# Bank1_DDR.net
KiCad netlist of a schematic drawn in Altium Designer
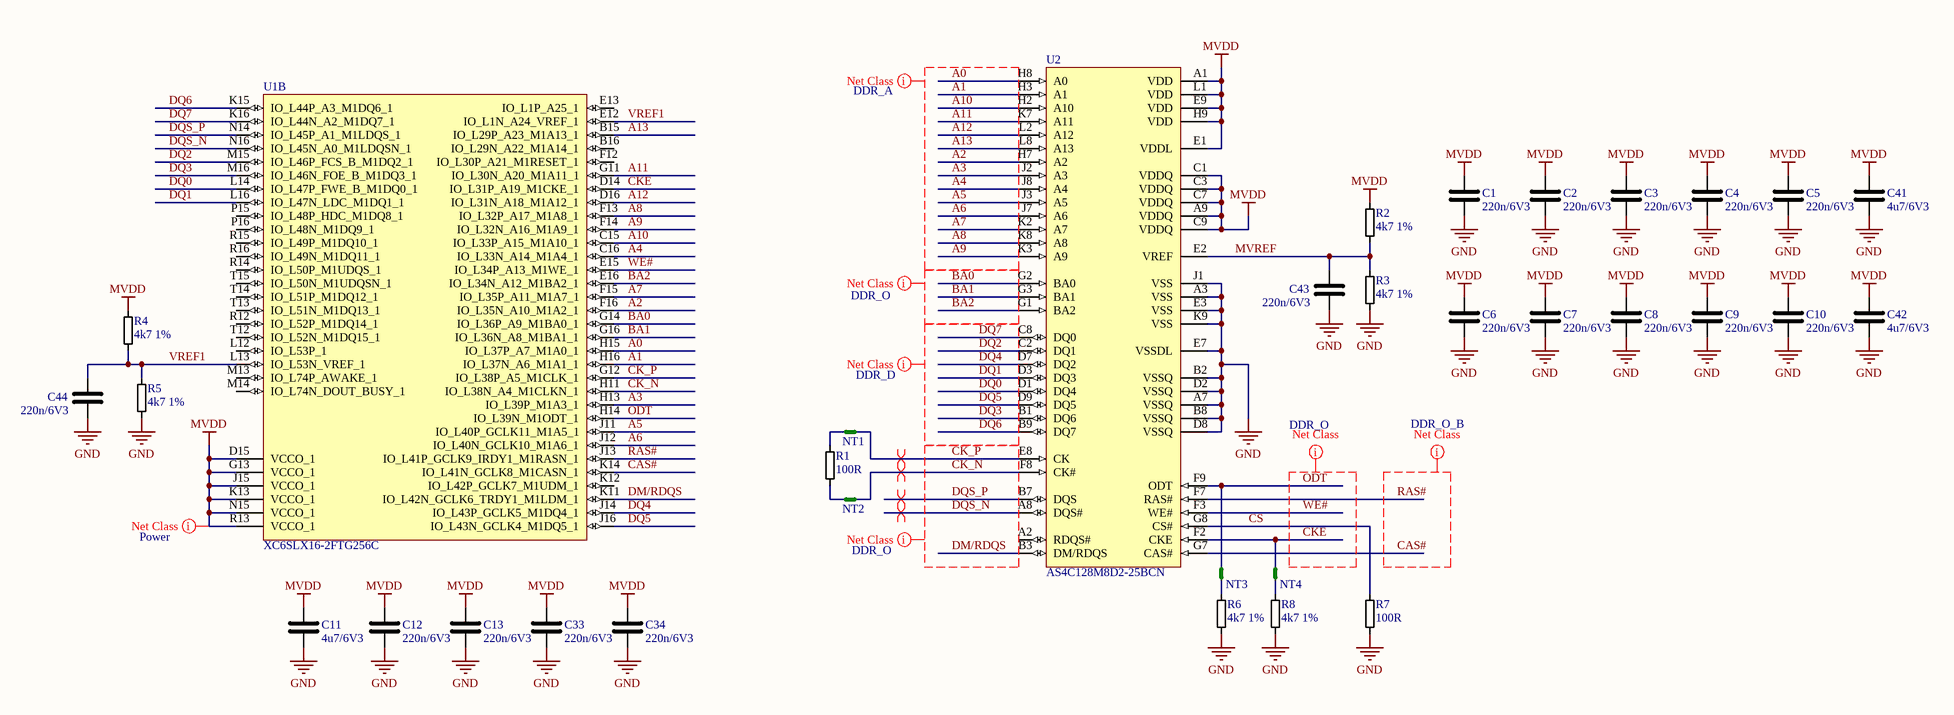
[diagram p0: Bank1_DDR.SchDoc]

(export (version "E")
  (design (tool "Eeschema 10.0.6"))
  (components
    (comp (ref "C1") (value "220n/6V3") (footprint "C0402_N") (libsource (lib "niceCircuits") (part "C")))
    (comp (ref "C2") (value "220n/6V3") (footprint "C0402_N") (libsource (lib "niceCircuits") (part "C")))
    (comp (ref "C3") (value "220n/6V3") (footprint "C0402_N") (libsource (lib "niceCircuits") (part "C")))
    (comp (ref "C4") (value "220n/6V3") (footprint "C0402_N") (libsource (lib "niceCircuits") (part "C")))
    (comp (ref "C5") (value "220n/6V3") (footprint "C0402_N") (libsource (lib "niceCircuits") (part "C")))
    (comp (ref "C6") (value "220n/6V3") (footprint "C0402_N") (libsource (lib "niceCircuits") (part "C")))
    (comp (ref "C7") (value "220n/6V3") (footprint "C0402_N") (libsource (lib "niceCircuits") (part "C")))
    (comp (ref "C8") (value "220n/6V3") (footprint "C0402_N") (libsource (lib "niceCircuits") (part "C")))
    (comp (ref "C9") (value "220n/6V3") (footprint "C0402_N") (libsource (lib "niceCircuits") (part "C")))
    (comp (ref "C10") (value "220n/6V3") (footprint "C0402_N") (libsource (lib "niceCircuits") (part "C")))
    (comp (ref "C11") (value "4u7/6V3") (footprint "C0805_N") (libsource (lib "niceCircuits") (part "C")))
    (comp (ref "C12") (value "220n/6V3") (footprint "C0402_N") (libsource (lib "niceCircuits") (part "C")))
    (comp (ref "C13") (value "220n/6V3") (footprint "C0402_N") (libsource (lib "niceCircuits") (part "C")))
    (comp (ref "C33") (value "220n/6V3") (footprint "C0402_N") (libsource (lib "niceCircuits") (part "C")))
    (comp (ref "C34") (value "220n/6V3") (footprint "C0402_N") (libsource (lib "niceCircuits") (part "C")))
    (comp (ref "C41") (value "4u7/6V3") (footprint "C0805_N") (libsource (lib "niceCircuits") (part "C")))
    (comp (ref "C42") (value "4u7/6V3") (footprint "C0805_N") (libsource (lib "niceCircuits") (part "C")))
    (comp (ref "C43") (value "220n/6V3") (footprint "C0402_N") (libsource (lib "niceCircuits") (part "C")))
    (comp (ref "C44") (value "220n/6V3") (footprint "C0402_N") (libsource (lib "niceCircuits") (part "C")))
    (comp (ref "NT1")
      (value "NET TIE")
      (footprint "NET_TIE_5MIL_2")
      (libsource (lib "niceCircuits") (part "NET TIE"))
    )
    (comp (ref "NT2")
      (value "NET TIE")
      (footprint "NET_TIE_5MIL_2")
      (libsource (lib "niceCircuits") (part "NET TIE"))
    )
    (comp (ref "NT3")
      (value "NET TIE")
      (footprint "NET_TIE_5MIL_2")
      (libsource (lib "niceCircuits") (part "NET TIE"))
    )
    (comp (ref "NT4")
      (value "NET TIE")
      (footprint "NET_TIE_5MIL_2")
      (libsource (lib "niceCircuits") (part "NET TIE"))
    )
    (comp (ref "R1") (value "100R") (footprint "R0402_N") (libsource (lib "niceCircuits") (part "R")))
    (comp (ref "R2") (value "4k7 1%") (footprint "R0402_N") (libsource (lib "niceCircuits") (part "R")))
    (comp (ref "R3") (value "4k7 1%") (footprint "R0402_N") (libsource (lib "niceCircuits") (part "R")))
    (comp (ref "R4") (value "4k7 1%") (footprint "R0402_N") (libsource (lib "niceCircuits") (part "R")))
    (comp (ref "R5") (value "4k7 1%") (footprint "R0402_N") (libsource (lib "niceCircuits") (part "R")))
    (comp (ref "R6") (value "4k7 1%") (footprint "R0402_N") (libsource (lib "niceCircuits") (part "R")))
    (comp (ref "R7") (value "100R") (footprint "R0402_N") (libsource (lib "niceCircuits") (part "R")))
    (comp (ref "R8") (value "4k7 1%") (footprint "R0402_N") (libsource (lib "niceCircuits") (part "R")))
    (comp (ref "U1")
      (value "XC6SLX16-2FTG256C")
      (footprint "Xilinx_FT256_L")
      (libsource (lib "niceCircuits") (part "XC6SLX16-2FTG256C"))
    )
    (comp (ref "U2")
      (value "AS4C128M8D2-25BCN")
      (footprint "Alliance_FBGA60")
      (libsource (lib "niceCircuits") (part "AS4C128M8D2-25BCN"))
    )
  )
  (nets
    (net (code "1") (name "/A0") (class "Default")
      (node (ref "U1") (pin "H15") (pinfunction "IO_L37P_A7_M1A0_1_H15") (pintype "bidirectional"))
      (node (ref "U2") (pin "H8") (pinfunction "A0_H8") (pintype "input"))
    )
    (net (code "2") (name "/A1") (class "Default")
      (node (ref "U1") (pin "H16") (pinfunction "IO_L37N_A6_M1A1_1_H16") (pintype "bidirectional"))
      (node (ref "U2") (pin "H3") (pinfunction "A1_H3") (pintype "input"))
    )
    (net (code "3") (name "/A2") (class "Default")
      (node (ref "U1") (pin "F16") (pinfunction "IO_L35N_A10_M1A2_1_F16") (pintype "bidirectional"))
      (node (ref "U2") (pin "H7") (pinfunction "A2_H7") (pintype "input"))
    )
    (net (code "4") (name "/A3") (class "Default")
      (node (ref "U1") (pin "H13") (pinfunction "IO_L39P_M1A3_1_H13") (pintype "bidirectional"))
      (node (ref "U2") (pin "J2") (pinfunction "A3_J2") (pintype "input"))
    )
    (net (code "5") (name "/A4") (class "Default")
      (node (ref "U1") (pin "C16") (pinfunction "IO_L33N_A14_M1A4_1_C16") (pintype "bidirectional"))
      (node (ref "U2") (pin "J8") (pinfunction "A4_J8") (pintype "input"))
    )
    (net (code "6") (name "/A5") (class "Default")
      (node (ref "U1") (pin "J11") (pinfunction "IO_L40P_GCLK11_M1A5_1_J11") (pintype "bidirectional"))
      (node (ref "U2") (pin "J3") (pinfunction "A5_J3") (pintype "input"))
    )
    (net (code "7") (name "/A6") (class "Default")
      (node (ref "U1") (pin "J12") (pinfunction "IO_L40N_GCLK10_M1A6_1_J12") (pintype "bidirectional"))
      (node (ref "U2") (pin "J7") (pinfunction "A6_J7") (pintype "input"))
    )
    (net (code "8") (name "/A7") (class "Default")
      (node (ref "U1") (pin "F15") (pinfunction "IO_L35P_A11_M1A7_1_F15") (pintype "bidirectional"))
      (node (ref "U2") (pin "K2") (pinfunction "A7_K2") (pintype "input"))
    )
    (net (code "9") (name "/A8") (class "Default")
      (node (ref "U1") (pin "F13") (pinfunction "IO_L32P_A17_M1A8_1_F13") (pintype "bidirectional"))
      (node (ref "U2") (pin "K8") (pinfunction "A8_K8") (pintype "input"))
    )
    (net (code "10") (name "/A9") (class "Default")
      (node (ref "U1") (pin "F14") (pinfunction "IO_L32N_A16_M1A9_1_F14") (pintype "bidirectional"))
      (node (ref "U2") (pin "K3") (pinfunction "A9_K3") (pintype "input"))
    )
    (net (code "11") (name "/A10") (class "Default")
      (node (ref "U1") (pin "C15") (pinfunction "IO_L33P_A15_M1A10_1_C15") (pintype "bidirectional"))
      (node (ref "U2") (pin "H2") (pinfunction "A10_H2") (pintype "input"))
    )
    (net (code "12") (name "/A11") (class "Default")
      (node (ref "U1") (pin "G11") (pinfunction "IO_L30N_A20_M1A11_1_G11") (pintype "bidirectional"))
      (node (ref "U2") (pin "K7") (pinfunction "A11_K7") (pintype "input"))
    )
    (net (code "13") (name "/A12") (class "Default")
      (node (ref "U1") (pin "D16") (pinfunction "IO_L31N_A18_M1A12_1_D16") (pintype "bidirectional"))
      (node (ref "U2") (pin "L2") (pinfunction "A12_L2") (pintype "input"))
    )
    (net (code "14") (name "/A13") (class "Default")
      (node (ref "U1") (pin "B15") (pinfunction "IO_L29P_A23_M1A13_1_B15") (pintype "bidirectional"))
      (node (ref "U2") (pin "L8") (pinfunction "A13_L8") (pintype "input"))
    )
    (net (code "15") (name "/BA0") (class "Default")
      (node (ref "U1") (pin "G14") (pinfunction "IO_L36P_A9_M1BA0_1_G14") (pintype "bidirectional"))
      (node (ref "U2") (pin "G2") (pinfunction "BA0_G2") (pintype "input"))
    )
    (net (code "16") (name "/BA1") (class "Default")
      (node (ref "U1") (pin "G16") (pinfunction "IO_L36N_A8_M1BA1_1_G16") (pintype "bidirectional"))
      (node (ref "U2") (pin "G3") (pinfunction "BA1_G3") (pintype "input"))
    )
    (net (code "17") (name "/BA2") (class "Default")
      (node (ref "U1") (pin "E16") (pinfunction "IO_L34N_A12_M1BA2_1_E16") (pintype "bidirectional"))
      (node (ref "U2") (pin "G1") (pinfunction "BA2_G1") (pintype "input"))
    )
    (net (code "18") (name "/CAS#") (class "Default")
      (node (ref "U1") (pin "K14") (pinfunction "IO_L41N_GCLK8_M1CASN_1_K14") (pintype "bidirectional"))
      (node (ref "U2") (pin "G7") (pinfunction "CAS#_G7") (pintype "input"))
    )
    (net (code "19") (name "/CKE") (class "Default")
      (node (ref "NT4") (pin "2") (pinfunction "2_2") (pintype "passive"))
      (node (ref "U1") (pin "D14") (pinfunction "IO_L31P_A19_M1CKE_1_D14") (pintype "bidirectional"))
      (node (ref "U2") (pin "F2") (pinfunction "CKE_F2") (pintype "input"))
    )
    (net (code "20") (name "/CK_N") (class "Default")
      (node (ref "NT2") (pin "2") (pinfunction "2_2") (pintype "passive"))
      (node (ref "U1") (pin "H11") (pinfunction "IO_L38N_A4_M1CLKN_1_H11") (pintype "bidirectional"))
      (node (ref "U2") (pin "F8") (pinfunction "CK#_F8") (pintype "input"))
    )
    (net (code "21") (name "/CK_P") (class "Default")
      (node (ref "NT1") (pin "2") (pinfunction "2_2") (pintype "passive"))
      (node (ref "U1") (pin "G12") (pinfunction "IO_L38P_A5_M1CLK_1_G12") (pintype "bidirectional"))
      (node (ref "U2") (pin "E8") (pinfunction "CK_E8") (pintype "input"))
    )
    (net (code "22") (name "/CS") (class "Default")
      (node (ref "R7") (pin "1") (pinfunction "1_1") (pintype "passive"))
      (node (ref "U2") (pin "G8") (pinfunction "CS#_G8") (pintype "input"))
    )
    (net (code "23") (name "/DM{slash}RDQS") (class "Default")
      (node (ref "U1") (pin "K11") (pinfunction "IO_L42N_GCLK6_TRDY1_M1LDM_1_K11") (pintype "bidirectional"))
      (node (ref "U2") (pin "B3") (pinfunction "DM/RDQS_B3") (pintype "bidirectional"))
    )
    (net (code "24") (name "/DQ0") (class "Default")
      (node (ref "U1") (pin "L14") (pinfunction "IO_L47P_FWE_B_M1DQ0_1_L14") (pintype "bidirectional"))
      (node (ref "U2") (pin "D1") (pinfunction "DQ4_D1") (pintype "bidirectional"))
    )
    (net (code "25") (name "/DQ1") (class "Default")
      (node (ref "U1") (pin "L16") (pinfunction "IO_L47N_LDC_M1DQ1_1_L16") (pintype "bidirectional"))
      (node (ref "U2") (pin "D3") (pinfunction "DQ3_D3") (pintype "bidirectional"))
    )
    (net (code "26") (name "/DQ2") (class "Default")
      (node (ref "U1") (pin "M15") (pinfunction "IO_L46P_FCS_B_M1DQ2_1_M15") (pintype "bidirectional"))
      (node (ref "U2") (pin "C2") (pinfunction "DQ1_C2") (pintype "bidirectional"))
    )
    (net (code "27") (name "/DQ3") (class "Default")
      (node (ref "U1") (pin "M16") (pinfunction "IO_L46N_FOE_B_M1DQ3_1_M16") (pintype "bidirectional"))
      (node (ref "U2") (pin "B1") (pinfunction "DQ6_B1") (pintype "bidirectional"))
    )
    (net (code "28") (name "/DQ4") (class "Default")
      (node (ref "U1") (pin "J14") (pinfunction "IO_L43P_GCLK5_M1DQ4_1_J14") (pintype "bidirectional"))
      (node (ref "U2") (pin "D7") (pinfunction "DQ2_D7") (pintype "bidirectional"))
    )
    (net (code "29") (name "/DQ5") (class "Default")
      (node (ref "U1") (pin "J16") (pinfunction "IO_L43N_GCLK4_M1DQ5_1_J16") (pintype "bidirectional"))
      (node (ref "U2") (pin "D9") (pinfunction "DQ5_D9") (pintype "bidirectional"))
    )
    (net (code "30") (name "/DQ6") (class "Default")
      (node (ref "U1") (pin "K15") (pinfunction "IO_L44P_A3_M1DQ6_1_K15") (pintype "bidirectional"))
      (node (ref "U2") (pin "B9") (pinfunction "DQ7_B9") (pintype "bidirectional"))
    )
    (net (code "31") (name "/DQ7") (class "Default")
      (node (ref "U1") (pin "K16") (pinfunction "IO_L44N_A2_M1DQ7_1_K16") (pintype "bidirectional"))
      (node (ref "U2") (pin "C8") (pinfunction "DQ0_C8") (pintype "bidirectional"))
    )
    (net (code "32") (name "/DQS_N") (class "Default")
      (node (ref "U1") (pin "N16") (pinfunction "IO_L45N_A0_M1LDQSN_1_N16") (pintype "bidirectional"))
      (node (ref "U2") (pin "A8") (pinfunction "DQS#_A8") (pintype "bidirectional"))
    )
    (net (code "33") (name "/DQS_P") (class "Default")
      (node (ref "U1") (pin "N14") (pinfunction "IO_L45P_A1_M1LDQS_1_N14") (pintype "bidirectional"))
      (node (ref "U2") (pin "B7") (pinfunction "DQS_B7") (pintype "bidirectional"))
    )
    (net (code "34") (name "/MVREF") (class "Default")
      (node (ref "C43") (pin "2") (pinfunction "2_2") (pintype "passive"))
      (node (ref "R2") (pin "2") (pinfunction "2_2") (pintype "passive"))
      (node (ref "R3") (pin "1") (pinfunction "1_1") (pintype "passive"))
      (node (ref "U2") (pin "E2") (pinfunction "VREF_E2") (pintype "power_in"))
    )
    (net (code "35") (name "/ODT") (class "Default")
      (node (ref "NT3") (pin "2") (pinfunction "2_2") (pintype "passive"))
      (node (ref "U1") (pin "H14") (pinfunction "IO_L39N_M1ODT_1_H14") (pintype "bidirectional"))
      (node (ref "U2") (pin "F9") (pinfunction "ODT_F9") (pintype "input"))
    )
    (net (code "36") (name "/RAS#") (class "Default")
      (node (ref "U1") (pin "J13") (pinfunction "IO_L41P_GCLK9_IRDY1_M1RASN_1_J13") (pintype "bidirectional"))
      (node (ref "U2") (pin "F7") (pinfunction "RAS#_F7") (pintype "input"))
    )
    (net (code "37") (name "/VREF1") (class "Default")
      (node (ref "C44") (pin "2") (pinfunction "2_2") (pintype "passive"))
      (node (ref "R4") (pin "2") (pinfunction "2_2") (pintype "passive"))
      (node (ref "R5") (pin "1") (pinfunction "1_1") (pintype "passive"))
      (node (ref "U1") (pin "E12") (pinfunction "IO_L1N_A24_VREF_1_E12") (pintype "bidirectional"))
      (node (ref "U1") (pin "L13") (pinfunction "IO_L53N_VREF_1_L13") (pintype "bidirectional"))
    )
    (net (code "38") (name "/WE#") (class "Default")
      (node (ref "U1") (pin "E15") (pinfunction "IO_L34P_A13_M1WE_1_E15") (pintype "bidirectional"))
      (node (ref "U2") (pin "F3") (pinfunction "WE#_F3") (pintype "input"))
    )
    (net (code "39") (name "GND") (class "Default")
      (node (ref "C1") (pin "1") (pinfunction "1_1") (pintype "passive"))
      (node (ref "C10") (pin "1") (pinfunction "1_1") (pintype "passive"))
      (node (ref "C11") (pin "1") (pinfunction "1_1") (pintype "passive"))
      (node (ref "C12") (pin "1") (pinfunction "1_1") (pintype "passive"))
      (node (ref "C13") (pin "1") (pinfunction "1_1") (pintype "passive"))
      (node (ref "C2") (pin "1") (pinfunction "1_1") (pintype "passive"))
      (node (ref "C3") (pin "1") (pinfunction "1_1") (pintype "passive"))
      (node (ref "C33") (pin "1") (pinfunction "1_1") (pintype "passive"))
      (node (ref "C34") (pin "1") (pinfunction "1_1") (pintype "passive"))
      (node (ref "C4") (pin "1") (pinfunction "1_1") (pintype "passive"))
      (node (ref "C41") (pin "1") (pinfunction "1_1") (pintype "passive"))
      (node (ref "C42") (pin "1") (pinfunction "1_1") (pintype "passive"))
      (node (ref "C43") (pin "1") (pinfunction "1_1") (pintype "passive"))
      (node (ref "C44") (pin "1") (pinfunction "1_1") (pintype "passive"))
      (node (ref "C5") (pin "1") (pinfunction "1_1") (pintype "passive"))
      (node (ref "C6") (pin "1") (pinfunction "1_1") (pintype "passive"))
      (node (ref "C7") (pin "1") (pinfunction "1_1") (pintype "passive"))
      (node (ref "C8") (pin "1") (pinfunction "1_1") (pintype "passive"))
      (node (ref "C9") (pin "1") (pinfunction "1_1") (pintype "passive"))
      (node (ref "R3") (pin "2") (pinfunction "2_2") (pintype "passive"))
      (node (ref "R5") (pin "2") (pinfunction "2_2") (pintype "passive"))
      (node (ref "R6") (pin "2") (pinfunction "2_2") (pintype "passive"))
      (node (ref "R7") (pin "2") (pinfunction "2_2") (pintype "passive"))
      (node (ref "R8") (pin "2") (pinfunction "2_2") (pintype "passive"))
      (node (ref "U2") (pin "A3") (pinfunction "VSS_A3") (pintype "power_in"))
      (node (ref "U2") (pin "A7") (pinfunction "VSSQ_A7") (pintype "power_in"))
      (node (ref "U2") (pin "B2") (pinfunction "VSSQ_B2") (pintype "power_in"))
      (node (ref "U2") (pin "B8") (pinfunction "VSSQ_B8") (pintype "power_in"))
      (node (ref "U2") (pin "D2") (pinfunction "VSSQ_D2") (pintype "power_in"))
      (node (ref "U2") (pin "D8") (pinfunction "VSSQ_D8") (pintype "power_in"))
      (node (ref "U2") (pin "E3") (pinfunction "VSS_E3") (pintype "power_in"))
      (node (ref "U2") (pin "E7") (pinfunction "VSSDL_E7") (pintype "power_in"))
      (node (ref "U2") (pin "J1") (pinfunction "VSS_J1") (pintype "power_in"))
      (node (ref "U2") (pin "K9") (pinfunction "VSS_K9") (pintype "power_in"))
    )
    (net (code "40") (name "MVDD") (class "Default")
      (node (ref "C1") (pin "2") (pinfunction "2_2") (pintype "passive"))
      (node (ref "C10") (pin "2") (pinfunction "2_2") (pintype "passive"))
      (node (ref "C11") (pin "2") (pinfunction "2_2") (pintype "passive"))
      (node (ref "C12") (pin "2") (pinfunction "2_2") (pintype "passive"))
      (node (ref "C13") (pin "2") (pinfunction "2_2") (pintype "passive"))
      (node (ref "C2") (pin "2") (pinfunction "2_2") (pintype "passive"))
      (node (ref "C3") (pin "2") (pinfunction "2_2") (pintype "passive"))
      (node (ref "C33") (pin "2") (pinfunction "2_2") (pintype "passive"))
      (node (ref "C34") (pin "2") (pinfunction "2_2") (pintype "passive"))
      (node (ref "C4") (pin "2") (pinfunction "2_2") (pintype "passive"))
      (node (ref "C41") (pin "2") (pinfunction "2_2") (pintype "passive"))
      (node (ref "C42") (pin "2") (pinfunction "2_2") (pintype "passive"))
      (node (ref "C5") (pin "2") (pinfunction "2_2") (pintype "passive"))
      (node (ref "C6") (pin "2") (pinfunction "2_2") (pintype "passive"))
      (node (ref "C7") (pin "2") (pinfunction "2_2") (pintype "passive"))
      (node (ref "C8") (pin "2") (pinfunction "2_2") (pintype "passive"))
      (node (ref "C9") (pin "2") (pinfunction "2_2") (pintype "passive"))
      (node (ref "R2") (pin "1") (pinfunction "1_1") (pintype "passive"))
      (node (ref "R4") (pin "1") (pinfunction "1_1") (pintype "passive"))
      (node (ref "U1") (pin "D15") (pinfunction "VCCO_1_D15") (pintype "power_in"))
      (node (ref "U1") (pin "G13") (pinfunction "VCCO_1_G13") (pintype "power_in"))
      (node (ref "U1") (pin "J15") (pinfunction "VCCO_1_J15") (pintype "power_in"))
      (node (ref "U1") (pin "K13") (pinfunction "VCCO_1_K13") (pintype "power_in"))
      (node (ref "U1") (pin "N15") (pinfunction "VCCO_1_N15") (pintype "power_in"))
      (node (ref "U1") (pin "R13") (pinfunction "VCCO_1_R13") (pintype "power_in"))
      (node (ref "U2") (pin "A1") (pinfunction "VDD_A1") (pintype "power_in"))
      (node (ref "U2") (pin "A9") (pinfunction "VDDQ_A9") (pintype "power_in"))
      (node (ref "U2") (pin "C1") (pinfunction "VDDQ_C1") (pintype "power_in"))
      (node (ref "U2") (pin "C3") (pinfunction "VDDQ_C3") (pintype "power_in"))
      (node (ref "U2") (pin "C7") (pinfunction "VDDQ_C7") (pintype "power_in"))
      (node (ref "U2") (pin "C9") (pinfunction "VDDQ_C9") (pintype "power_in"))
      (node (ref "U2") (pin "E1") (pinfunction "VDDL_E1") (pintype "power_in"))
      (node (ref "U2") (pin "E9") (pinfunction "VDD_E9") (pintype "power_in"))
      (node (ref "U2") (pin "H9") (pinfunction "VDD_H9") (pintype "power_in"))
      (node (ref "U2") (pin "L1") (pinfunction "VDD_L1") (pintype "power_in"))
    )
    (net (code "41") (name "Net-(NT1-Pad1)") (class "Default")
      (node (ref "NT1") (pin "1") (pinfunction "1_1") (pintype "passive"))
      (node (ref "R1") (pin "1") (pinfunction "1_1") (pintype "passive"))
    )
    (net (code "42") (name "Net-(NT2-Pad1)") (class "Default")
      (node (ref "NT2") (pin "1") (pinfunction "1_1") (pintype "passive"))
      (node (ref "R1") (pin "2") (pinfunction "2_2") (pintype "passive"))
    )
    (net (code "43") (name "Net-(NT3-Pad1)") (class "Default")
      (node (ref "NT3") (pin "1") (pinfunction "1_1") (pintype "passive"))
      (node (ref "R6") (pin "1") (pinfunction "1_1") (pintype "passive"))
    )
    (net (code "44") (name "Net-(NT4-Pad1)") (class "Default")
      (node (ref "NT4") (pin "1") (pinfunction "1_1") (pintype "passive"))
      (node (ref "R8") (pin "1") (pinfunction "1_1") (pintype "passive"))
    )
    (net (code "45") (name "unconnected-(U1B-IO_L1P_A25_1-PadE13)") (class "Default")
      (node (ref "U1") (pin "E13") (pinfunction "IO_L1P_A25_1_E13") (pintype "bidirectional"))
    )
    (net (code "46") (name "unconnected-(U1B-IO_L29N_A22_M1A14_1-PadB16)") (class "Default")
      (node (ref "U1") (pin "B16") (pinfunction "IO_L29N_A22_M1A14_1_B16") (pintype "bidirectional"))
    )
    (net (code "47") (name "unconnected-(U1B-IO_L30P_A21_M1RESET_1-PadF12)") (class "Default")
      (node (ref "U1") (pin "F12") (pinfunction "IO_L30P_A21_M1RESET_1_F12") (pintype "bidirectional"))
    )
    (net (code "48") (name "unconnected-(U1B-IO_L42P_GCLK7_M1UDM_1-PadK12)") (class "Default")
      (node (ref "U1") (pin "K12") (pinfunction "IO_L42P_GCLK7_M1UDM_1_K12") (pintype "bidirectional"))
    )
    (net (code "49") (name "unconnected-(U1B-IO_L48N_M1DQ9_1-PadP16)") (class "Default")
      (node (ref "U1") (pin "P16") (pinfunction "IO_L48N_M1DQ9_1_P16") (pintype "bidirectional"))
    )
    (net (code "50") (name "unconnected-(U1B-IO_L48P_HDC_M1DQ8_1-PadP15)") (class "Default")
      (node (ref "U1") (pin "P15") (pinfunction "IO_L48P_HDC_M1DQ8_1_P15") (pintype "bidirectional"))
    )
    (net (code "51") (name "unconnected-(U1B-IO_L49N_M1DQ11_1-PadR16)") (class "Default")
      (node (ref "U1") (pin "R16") (pinfunction "IO_L49N_M1DQ11_1_R16") (pintype "bidirectional"))
    )
    (net (code "52") (name "unconnected-(U1B-IO_L49P_M1DQ10_1-PadR15)") (class "Default")
      (node (ref "U1") (pin "R15") (pinfunction "IO_L49P_M1DQ10_1_R15") (pintype "bidirectional"))
    )
    (net (code "53") (name "unconnected-(U1B-IO_L50N_M1UDQSN_1-PadT15)") (class "Default")
      (node (ref "U1") (pin "T15") (pinfunction "IO_L50N_M1UDQSN_1_T15") (pintype "bidirectional"))
    )
    (net (code "54") (name "unconnected-(U1B-IO_L50P_M1UDQS_1-PadR14)") (class "Default")
      (node (ref "U1") (pin "R14") (pinfunction "IO_L50P_M1UDQS_1_R14") (pintype "bidirectional"))
    )
    (net (code "55") (name "unconnected-(U1B-IO_L51N_M1DQ13_1-PadT13)") (class "Default")
      (node (ref "U1") (pin "T13") (pinfunction "IO_L51N_M1DQ13_1_T13") (pintype "bidirectional"))
    )
    (net (code "56") (name "unconnected-(U1B-IO_L51P_M1DQ12_1-PadT14)") (class "Default")
      (node (ref "U1") (pin "T14") (pinfunction "IO_L51P_M1DQ12_1_T14") (pintype "bidirectional"))
    )
    (net (code "57") (name "unconnected-(U1B-IO_L52N_M1DQ15_1-PadT12)") (class "Default")
      (node (ref "U1") (pin "T12") (pinfunction "IO_L52N_M1DQ15_1_T12") (pintype "bidirectional"))
    )
    (net (code "58") (name "unconnected-(U1B-IO_L52P_M1DQ14_1-PadR12)") (class "Default")
      (node (ref "U1") (pin "R12") (pinfunction "IO_L52P_M1DQ14_1_R12") (pintype "bidirectional"))
    )
    (net (code "59") (name "unconnected-(U1B-IO_L53P_1-PadL12)") (class "Default")
      (node (ref "U1") (pin "L12") (pinfunction "IO_L53P_1_L12") (pintype "bidirectional"))
    )
    (net (code "60") (name "unconnected-(U1B-IO_L74N_DOUT_BUSY_1-PadM14)") (class "Default")
      (node (ref "U1") (pin "M14") (pinfunction "IO_L74N_DOUT_BUSY_1_M14") (pintype "bidirectional"))
    )
    (net (code "61") (name "unconnected-(U1B-IO_L74P_AWAKE_1-PadM13)") (class "Default")
      (node (ref "U1") (pin "M13") (pinfunction "IO_L74P_AWAKE_1_M13") (pintype "bidirectional"))
    )
    (net (code "62") (name "unconnected-(U2-RDQS#-PadA2)") (class "Default")
      (node (ref "U2") (pin "A2") (pinfunction "RDQS#_A2") (pintype "bidirectional"))
    )
  )
)
